# TD_DAC.net
KiCad netlist of a schematic drawn in EAGLE
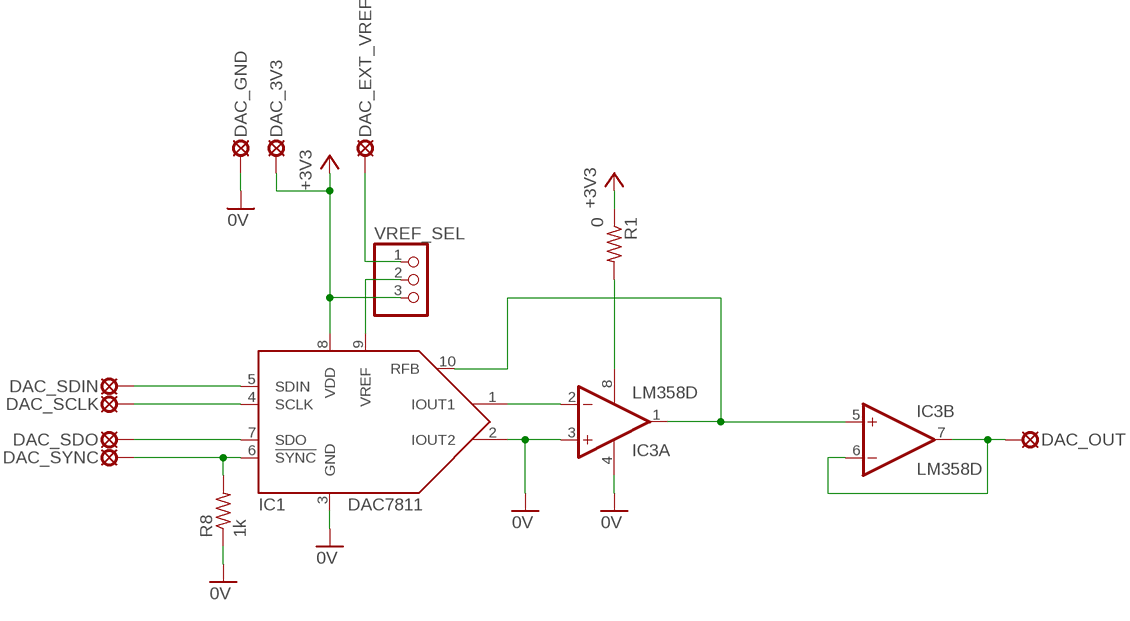
[diagram p0: schematic, sheet 1]

(export (version "E")
  (design (tool "Eeschema 10.0.6"))
  (components
    (comp (ref "DAC_3V3")
      (value "LSP10")
      (footprint "eagle-import:LSP10")
      (libsource (lib "eagle-import") (part "LSP10"))
    )
    (comp (ref "DAC_EXT_VREF")
      (value "LSP10")
      (footprint "eagle-import:LSP10")
      (libsource (lib "eagle-import") (part "LSP10"))
    )
    (comp (ref "DAC_GND")
      (value "LSP10")
      (footprint "eagle-import:LSP10")
      (libsource (lib "eagle-import") (part "LSP10"))
    )
    (comp (ref "DAC_OUT")
      (value "LSP10")
      (footprint "eagle-import:LSP10")
      (libsource (lib "eagle-import") (part "LSP10"))
    )
    (comp (ref "DAC_SCLK")
      (value "LSP10")
      (footprint "eagle-import:LSP10")
      (libsource (lib "eagle-import") (part "LSP10"))
    )
    (comp (ref "DAC_SDIN")
      (value "LSP10")
      (footprint "eagle-import:LSP10")
      (libsource (lib "eagle-import") (part "LSP10"))
    )
    (comp (ref "DAC_SDO")
      (value "LSP10")
      (footprint "eagle-import:LSP10")
      (libsource (lib "eagle-import") (part "LSP10"))
    )
    (comp (ref "DAC_SYNC")
      (value "LSP10")
      (footprint "eagle-import:LSP10")
      (libsource (lib "eagle-import") (part "LSP10"))
    )
    (comp (ref "IC1")
      (value "DAC7811")
      (footprint "eagle-import:S-PDSO-G10")
      (libsource (lib "eagle-import") (part "DAC7811"))
    )
    (comp (ref "IC3")
      (value "LM358D")
      (footprint "eagle-import:SO08")
      (libsource (lib "eagle-import") (part "LM358D"))
    )
    (comp (ref "R1")
      (value "0")
      (footprint "eagle-import:R1206")
      (libsource (lib "eagle-import") (part "R-US_R1206"))
    )
    (comp (ref "R8")
      (value "1k")
      (footprint "eagle-import:R0805")
      (libsource (lib "eagle-import") (part "R-US_R0805"))
    )
    (comp (ref "VREF_SEL")
      (value "PINHD-1X3")
      (footprint "eagle-import:1X03")
      (libsource (lib "eagle-import") (part "PINHD-1X3"))
    )
  )
  (nets
    (net (code "1") (name "+3V3") (class "Default")
      (node (ref "DAC_3V3") (pin "MP") (pinfunction "MP_MP") (pintype "passive"))
      (node (ref "IC1") (pin "8") (pinfunction "VDD_8") (pintype "bidirectional"))
      (node (ref "R1") (pin "1") (pinfunction "1_1") (pintype "passive"))
      (node (ref "VREF_SEL") (pin "3") (pinfunction "3_3") (pintype "passive"))
    )
    (net (code "2") (name "0V") (class "Default")
      (node (ref "DAC_GND") (pin "MP") (pinfunction "MP_MP") (pintype "passive"))
      (node (ref "IC1") (pin "2") (pinfunction "IOUT2_2") (pintype "bidirectional"))
      (node (ref "IC1") (pin "3") (pinfunction "GND_3") (pintype "bidirectional"))
      (node (ref "IC3") (pin "3") (pinfunction "+IN_3") (pintype "input"))
      (node (ref "IC3") (pin "4") (pinfunction "V-_4") (pintype "power_in"))
      (node (ref "R8") (pin "1") (pinfunction "1_1") (pintype "passive"))
    )
    (net (code "3") (name "Net-(DAC_EXT_VREF-PadMP)") (class "Default")
      (node (ref "DAC_EXT_VREF") (pin "MP") (pinfunction "MP_MP") (pintype "passive"))
      (node (ref "VREF_SEL") (pin "1") (pinfunction "1_1") (pintype "passive"))
    )
    (net (code "4") (name "Net-(IC1-IOUT1)") (class "Default")
      (node (ref "IC1") (pin "1") (pinfunction "IOUT1_1") (pintype "bidirectional"))
      (node (ref "IC3") (pin "2") (pinfunction "-IN_2") (pintype "input"))
    )
    (net (code "5") (name "Net-(IC1-RFB)") (class "Default")
      (node (ref "IC1") (pin "10") (pinfunction "RFB_10") (pintype "bidirectional"))
      (node (ref "IC3") (pin "1") (pinfunction "OUT_1") (pintype "output"))
      (node (ref "IC3") (pin "5") (pinfunction "+IN_5") (pintype "input"))
    )
    (net (code "6") (name "Net-(IC1-SCLK)") (class "Default")
      (node (ref "DAC_SCLK") (pin "MP") (pinfunction "MP_MP") (pintype "passive"))
      (node (ref "IC1") (pin "4") (pinfunction "SCLK_4") (pintype "bidirectional"))
    )
    (net (code "7") (name "Net-(IC1-SDIN)") (class "Default")
      (node (ref "DAC_SDIN") (pin "MP") (pinfunction "MP_MP") (pintype "passive"))
      (node (ref "IC1") (pin "5") (pinfunction "SDIN_5") (pintype "bidirectional"))
    )
    (net (code "8") (name "Net-(IC1-SDO)") (class "Default")
      (node (ref "DAC_SDO") (pin "MP") (pinfunction "MP_MP") (pintype "passive"))
      (node (ref "IC1") (pin "7") (pinfunction "SDO_7") (pintype "bidirectional"))
    )
    (net (code "9") (name "Net-(IC1-VREF)") (class "Default")
      (node (ref "IC1") (pin "9") (pinfunction "VREF_9") (pintype "bidirectional"))
      (node (ref "VREF_SEL") (pin "2") (pinfunction "2_2") (pintype "passive"))
    )
    (net (code "10") (name "Net-(IC1-~{SYNC})") (class "Default")
      (node (ref "DAC_SYNC") (pin "MP") (pinfunction "MP_MP") (pintype "passive"))
      (node (ref "IC1") (pin "6") (pinfunction "~{SYNC}_6") (pintype "bidirectional"))
      (node (ref "R8") (pin "2") (pinfunction "2_2") (pintype "passive"))
    )
    (net (code "11") (name "Net-(IC3B--IN)") (class "Default")
      (node (ref "DAC_OUT") (pin "MP") (pinfunction "MP_MP") (pintype "passive"))
      (node (ref "IC3") (pin "6") (pinfunction "-IN_6") (pintype "input"))
      (node (ref "IC3") (pin "7") (pinfunction "OUT_7") (pintype "output"))
    )
    (net (code "12") (name "Net-(IC3C-V+)") (class "Default")
      (node (ref "IC3") (pin "8") (pinfunction "V+_8") (pintype "power_in"))
      (node (ref "R1") (pin "2") (pinfunction "2_2") (pintype "passive"))
    )
  )
)
